# SolarPoints.net
KiCad netlist of a schematic drawn in EAGLE
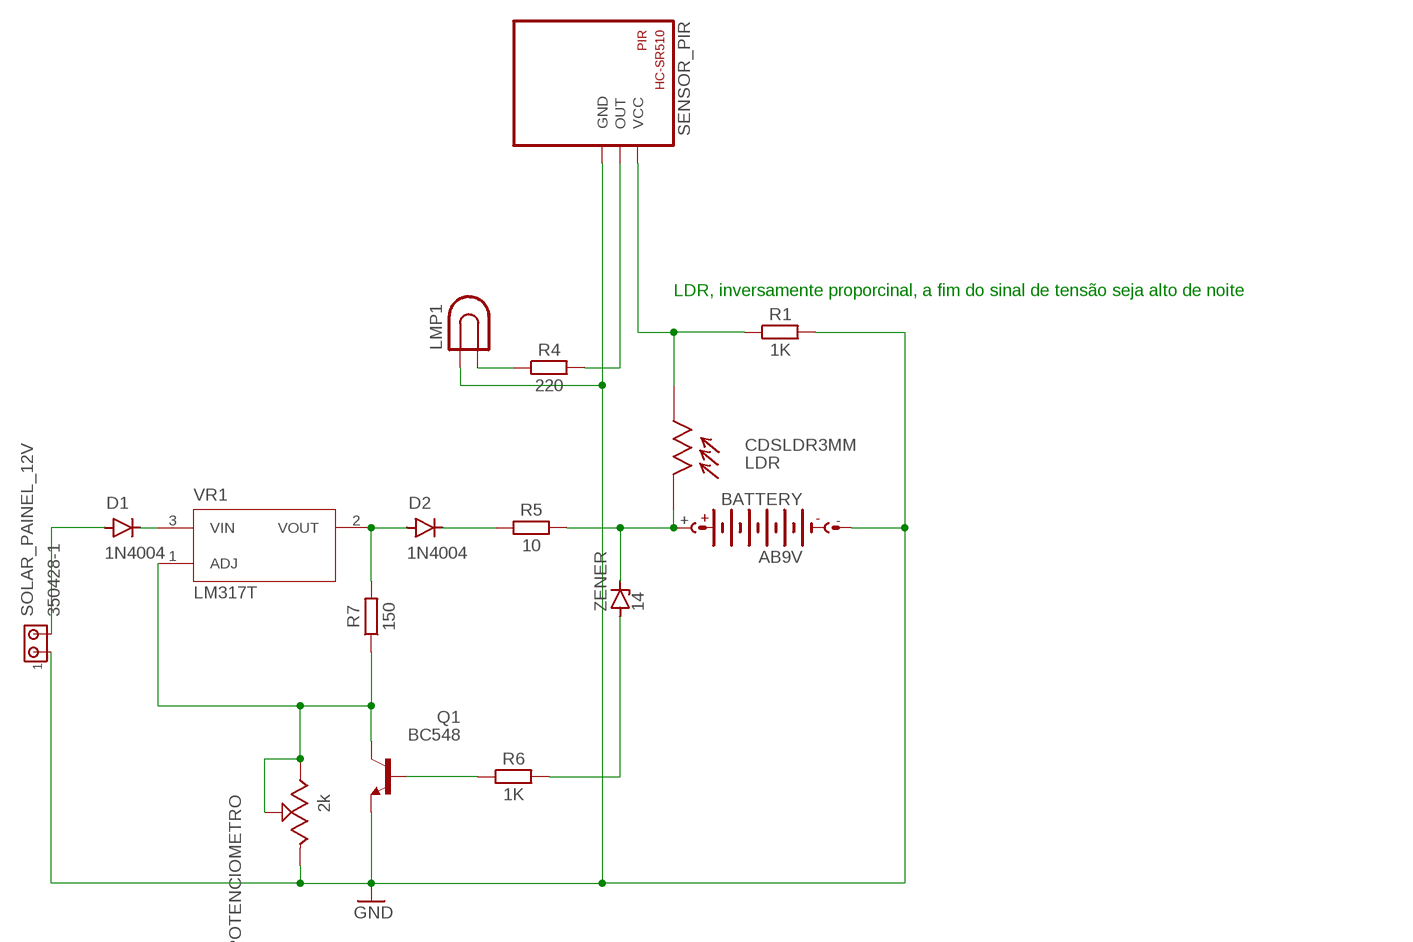
[diagram p0: schematic, sheet 1]

(export (version "E")
  (design (tool "Eeschema 10.0.6"))
  (components
    (comp (ref "BATTERY")
      (value "AB9V")
      (footprint "eagle-import:AB9V")
      (libsource (lib "eagle-import") (part "AB9V"))
    )
    (comp (ref "D1")
      (value "1N4004")
      (footprint "eagle-import:DO-41")
      (fields
        (field (name "DIGIKEY_PART_NUMBER") "1N4004MSCT-ND")
        (field (name "MANUFACTURER") "Micro Commercial Co")
        (field (name "CREATED_BY") "PCBLayout.com")
      )
      (libsource (lib "eagle-import") (part "1N4004"))
    )
    (comp (ref "D2")
      (value "1N4004")
      (footprint "eagle-import:DO-41")
      (fields
        (field (name "DIGIKEY_PART_NUMBER") "1N4004MSCT-ND")
        (field (name "MANUFACTURER") "Micro Commercial Co")
        (field (name "CREATED_BY") "PCBLayout.com")
      )
      (libsource (lib "eagle-import") (part "1N4004"))
    )
    (comp (ref "LDR")
      (value "CDSLDR3MM")
      (footprint "eagle-import:LDR3MM")
      (libsource (lib "eagle-import") (part "CDSLDR3MM"))
    )
    (comp (ref "LMP1")
      (value "LAMP")
      (footprint "eagle-import:LDH-5R")
      (libsource (lib "eagle-import") (part "LAMP"))
    )
    (comp (ref "POTENCIOMETRO")
      (value "2k")
      (footprint "eagle-import:91A1A-B28-B15L-ND")
      (fields
        (field (name "DIGIKEY_PARTNO") "91A1A-B28-B15L-ND")
        (field (name "MANUFACTURER") "Bourns Inc.")
        (field (name "MPN") "91A1A-B28-B15L")
        (field (name "CREATED_BY") "PCBLayout.com")
      )
      (libsource (lib "eagle-import") (part "91A1A-B28-B15L"))
    )
    (comp (ref "Q1")
      (value "BC548")
      (footprint "eagle-import:TO92-EBC")
      (libsource (lib "eagle-import") (part "BC548"))
    )
    (comp (ref "R1")
      (value "1K")
      (footprint "eagle-import:RESAD1016W63L850D250B")
      (libsource (lib "eagle-import") (part "RESISTOR_AXIAL-10.16MM-PITCH"))
    )
    (comp (ref "R4")
      (value "220")
      (footprint "eagle-import:RESAD1016W63L850D250B")
      (libsource (lib "eagle-import") (part "RESISTOR_AXIAL-10.16MM-PITCH"))
    )
    (comp (ref "R5")
      (value "10")
      (footprint "eagle-import:RESAD1016W63L850D250B")
      (libsource (lib "eagle-import") (part "RESISTOR_AXIAL-10.16MM-PITCH"))
    )
    (comp (ref "R6")
      (value "1K")
      (footprint "eagle-import:RESAD1016W63L850D250B")
      (libsource (lib "eagle-import") (part "RESISTOR_AXIAL-10.16MM-PITCH"))
    )
    (comp (ref "R7")
      (value "150")
      (footprint "eagle-import:RESAD1016W63L850D250B")
      (libsource (lib "eagle-import") (part "RESISTOR_AXIAL-10.16MM-PITCH"))
    )
    (comp (ref "SENSOR_PIR")
      (value "HC-SR501")
      (footprint "eagle-import:HC-SR501")
      (libsource (lib "eagle-import") (part "HC-SR501"))
    )
    (comp (ref "SOLAR_PAINEL_12V")
      (value "350428-1")
      (footprint "eagle-import:350428-1")
      (libsource (lib "eagle-import") (part "350428-1"))
    )
    (comp (ref "VR1")
      (value "LM317T")
      (footprint "eagle-import:TO254P1054X470X1955-3")
      (fields (field (name "MF") "Texas Instruments"))
      (libsource (lib "eagle-import") (part "LM317T"))
    )
    (comp (ref "ZENER")
      (value "14")
      (footprint "eagle-import:DO34Z7")
      (fields (field (name "SPICEPREFIX") "B"))
      (libsource (lib "eagle-import") (part "BZV10"))
    )
  )
  (nets
    (net (code "1") (name "GND") (class "Default")
      (node (ref "BATTERY") (pin "-") (pinfunction "-_-") (pintype "passive"))
      (node (ref "LMP1") (pin "1") (pinfunction "1_1") (pintype "passive"))
      (node (ref "POTENCIOMETRO") (pin "1") (pinfunction "1_1") (pintype "passive"))
      (node (ref "Q1") (pin "E") (pinfunction "E_E") (pintype "passive"))
      (node (ref "R1") (pin "2") (pinfunction "2_2") (pintype "passive"))
      (node (ref "SENSOR_PIR") (pin "GND") (pinfunction "GND_GND") (pintype "power_in"))
      (node (ref "SOLAR_PAINEL_12V") (pin "1") (pinfunction "1_1") (pintype "passive"))
    )
    (net (code "2") (name "Net-(BATTERY-Pad+)") (class "Default")
      (node (ref "BATTERY") (pin "+") (pinfunction "+_+") (pintype "passive"))
      (node (ref "LDR") (pin "P$1") (pinfunction "P$1_P$1") (pintype "bidirectional"))
      (node (ref "R5") (pin "2") (pinfunction "2_2") (pintype "passive"))
      (node (ref "ZENER") (pin "C") (pinfunction "C_C") (pintype "passive"))
    )
    (net (code "3") (name "Net-(D1-PadA)") (class "Default")
      (node (ref "D1") (pin "A") (pinfunction "A_A") (pintype "passive"))
      (node (ref "SOLAR_PAINEL_12V") (pin "2") (pinfunction "2_2") (pintype "passive"))
    )
    (net (code "4") (name "Net-(D2-PadC)") (class "Default")
      (node (ref "D2") (pin "C") (pinfunction "C_C") (pintype "passive"))
      (node (ref "R5") (pin "1") (pinfunction "1_1") (pintype "passive"))
    )
    (net (code "5") (name "Net-(LDR-PadP$2)") (class "Default")
      (node (ref "LDR") (pin "P$2") (pinfunction "P$2_P$2") (pintype "bidirectional"))
      (node (ref "R1") (pin "1") (pinfunction "1_1") (pintype "passive"))
      (node (ref "SENSOR_PIR") (pin "VCC") (pinfunction "VCC_VCC") (pintype "power_in"))
    )
    (net (code "6") (name "Net-(LMP1-Pad2)") (class "Default")
      (node (ref "LMP1") (pin "2") (pinfunction "2_2") (pintype "passive"))
      (node (ref "R4") (pin "1") (pinfunction "1_1") (pintype "passive"))
    )
    (net (code "7") (name "Net-(Q1-PadB)") (class "Default")
      (node (ref "Q1") (pin "B") (pinfunction "B_B") (pintype "passive"))
      (node (ref "R6") (pin "1") (pinfunction "1_1") (pintype "passive"))
    )
    (net (code "8") (name "Net-(R4-Pad2)") (class "Default")
      (node (ref "R4") (pin "2") (pinfunction "2_2") (pintype "passive"))
      (node (ref "SENSOR_PIR") (pin "OUT") (pinfunction "OUT_OUT") (pintype "bidirectional"))
    )
    (net (code "9") (name "Net-(R6-Pad2)") (class "Default")
      (node (ref "R6") (pin "2") (pinfunction "2_2") (pintype "passive"))
      (node (ref "ZENER") (pin "A") (pinfunction "A_A") (pintype "passive"))
    )
    (net (code "10") (name "Net-(VR1-ADJ)") (class "Default")
      (node (ref "POTENCIOMETRO") (pin "2") (pinfunction "2_2") (pintype "passive"))
      (node (ref "POTENCIOMETRO") (pin "3") (pinfunction "3_3") (pintype "passive"))
      (node (ref "Q1") (pin "C") (pinfunction "C_C") (pintype "passive"))
      (node (ref "R7") (pin "1") (pinfunction "1_1") (pintype "passive"))
      (node (ref "VR1") (pin "1") (pinfunction "ADJ_1") (pintype "input"))
    )
    (net (code "11") (name "Net-(VR1-VIN)") (class "Default")
      (node (ref "D1") (pin "C") (pinfunction "C_C") (pintype "passive"))
      (node (ref "VR1") (pin "3") (pinfunction "VIN_3") (pintype "input"))
    )
    (net (code "12") (name "Net-(VR1-VOUT)") (class "Default")
      (node (ref "D2") (pin "A") (pinfunction "A_A") (pintype "passive"))
      (node (ref "R7") (pin "2") (pinfunction "2_2") (pintype "passive"))
      (node (ref "VR1") (pin "2") (pinfunction "VOUT_2") (pintype "output"))
    )
  )
)
